# OpenROV_Light_Board_2_8.net
KiCad netlist of a schematic drawn in EAGLE
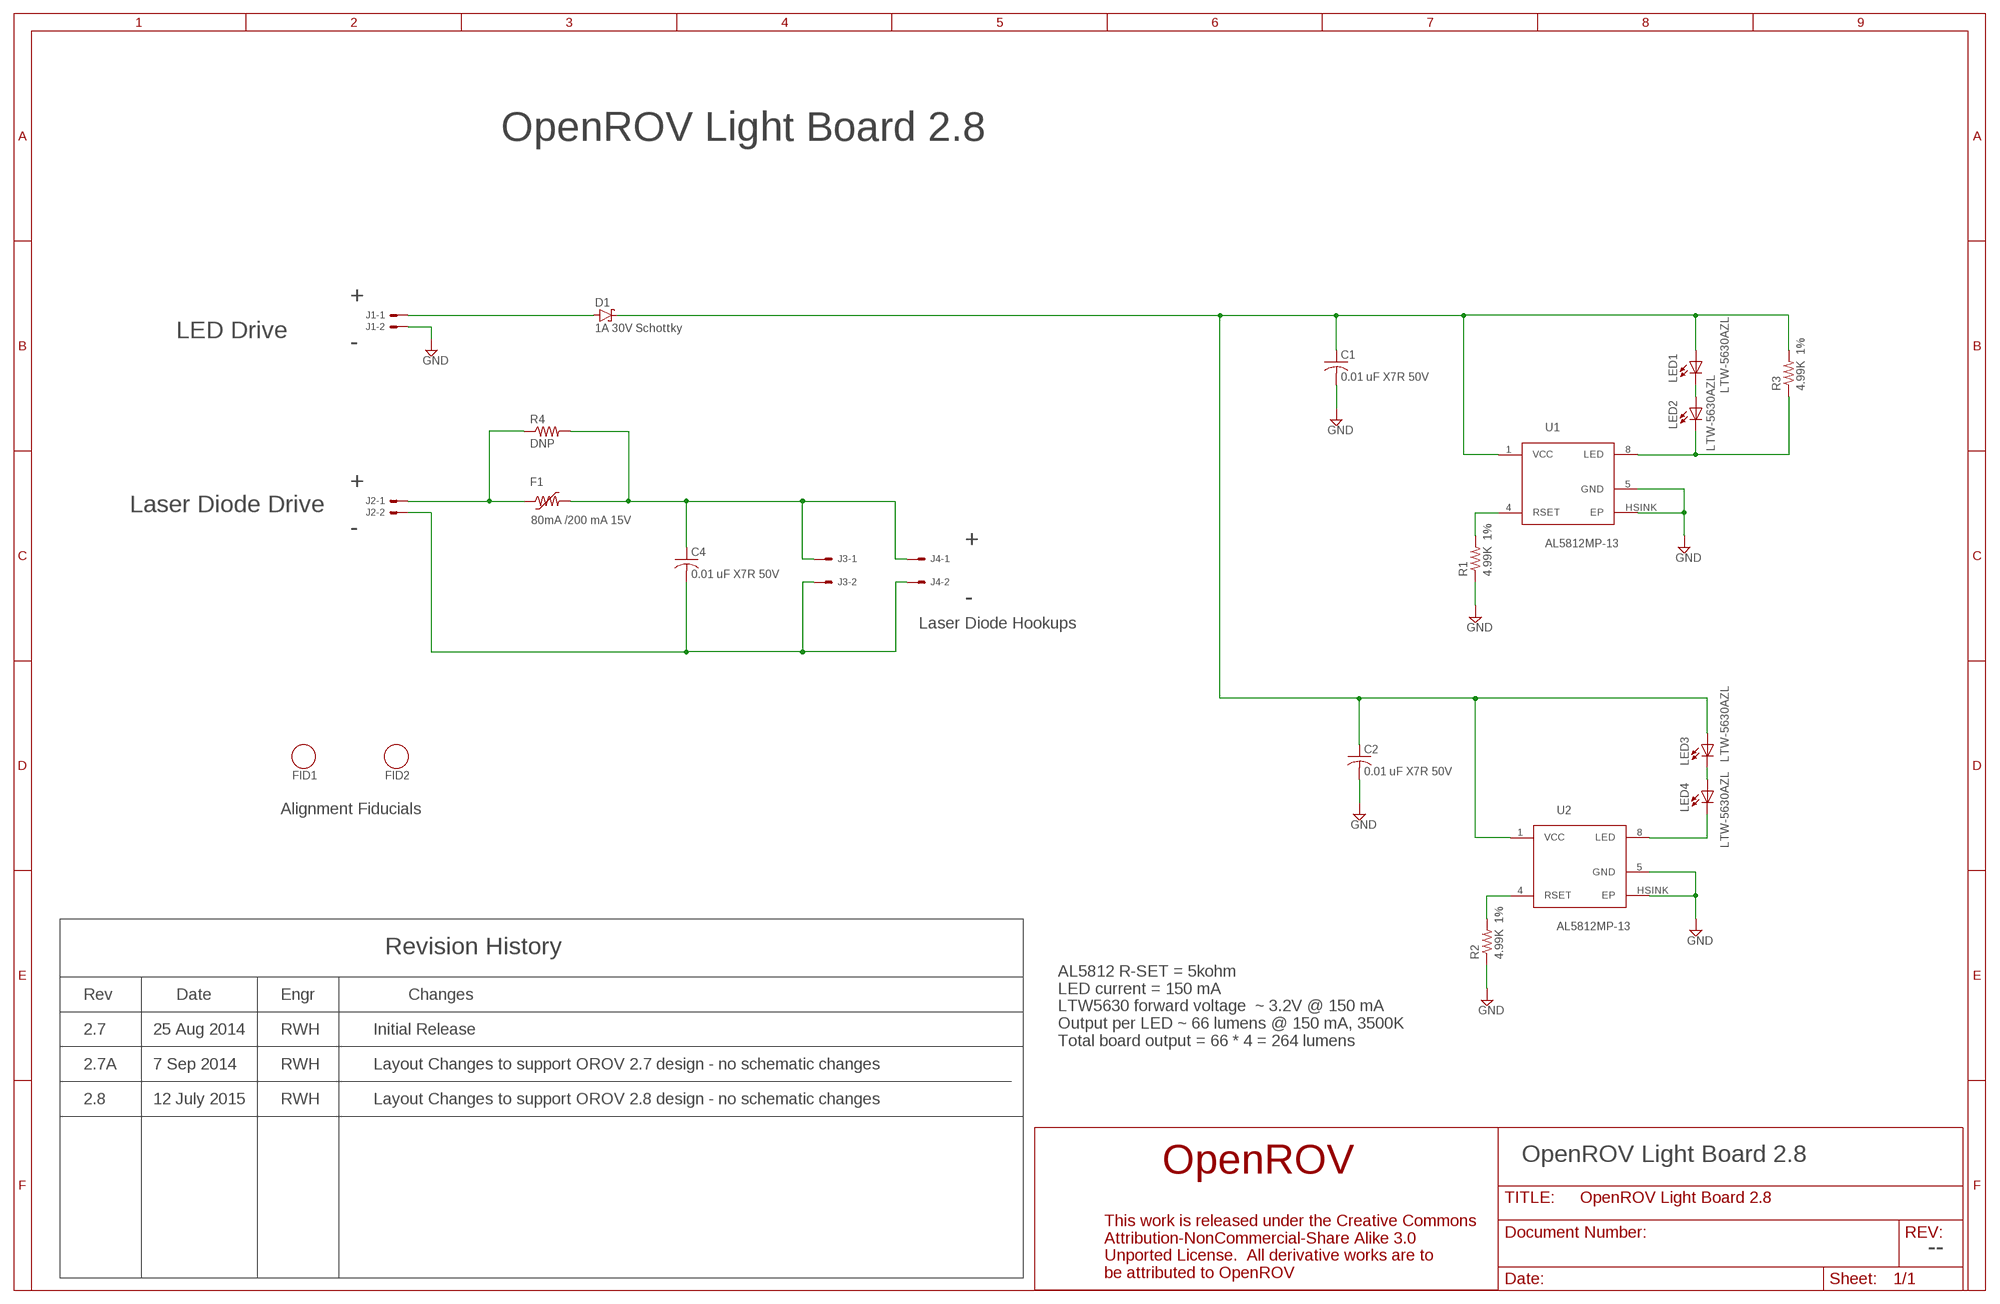
[diagram p0: schematic, sheet 1]

(export (version "E")
  (design (tool "Eeschema 10.0.6"))
  (components
    (comp (ref "C1")
      (value "0.01 uF X7R 50V")
      (footprint "eagle-import:R0603")
      (libsource (lib "eagle-import") (part "CAP0603"))
    )
    (comp (ref "C2")
      (value "0.01 uF X7R 50V")
      (footprint "eagle-import:R0603")
      (libsource (lib "eagle-import") (part "CAP0603"))
    )
    (comp (ref "C4")
      (value "0.01 uF X7R 50V")
      (footprint "eagle-import:R0603")
      (libsource (lib "eagle-import") (part "CAP0603"))
    )
    (comp (ref "D1")
      (value "1A 30V Schottky")
      (footprint "eagle-import:DO214AC")
      (libsource (lib "eagle-import") (part "SCHOTTKYDO214AC"))
    )
    (comp (ref "F1")
      (value "80mA /200 mA 15V")
      (footprint "eagle-import:R0603")
      (libsource (lib "eagle-import") (part "POLYFUSE-0603"))
    )
    (comp (ref "FID1")
      (value "FIDUCIAL_1")
      (footprint "eagle-import:FIDUCIAL_1")
      (libsource (lib "eagle-import") (part "FIDUCIAL_1"))
    )
    (comp (ref "FID2")
      (value "FIDUCIAL_1")
      (footprint "eagle-import:FIDUCIAL_1")
      (libsource (lib "eagle-import") (part "FIDUCIAL_1"))
    )
    (comp (ref "J1")
      (value "SOLDER_PADS_3MM")
      (footprint "eagle-import:SOLDER_PADS_3MM")
      (libsource (lib "eagle-import") (part "SOLDER_PADS_3MM"))
    )
    (comp (ref "J2")
      (value "SOLDER_PADS_3MM")
      (footprint "eagle-import:SOLDER_PADS_3MM")
      (libsource (lib "eagle-import") (part "SOLDER_PADS_3MM"))
    )
    (comp (ref "J3")
      (value "SOLDER_PADS_3MM-SMALL_HOLE")
      (footprint "eagle-import:SOLDER_PADS_3MM_SMALL_HOLE")
      (libsource (lib "eagle-import") (part "SOLDER_PADS_3MM-SMALL_HOLE"))
    )
    (comp (ref "J4")
      (value "SOLDER_PADS_3MM-SMALL_HOLE")
      (footprint "eagle-import:SOLDER_PADS_3MM_SMALL_HOLE")
      (libsource (lib "eagle-import") (part "SOLDER_PADS_3MM-SMALL_HOLE"))
    )
    (comp (ref "LED1")
      (value "LTW-5630AZL")
      (footprint "eagle-import:LITEON-5630")
      (libsource (lib "eagle-import") (part "LTW-5630AZL"))
    )
    (comp (ref "LED2")
      (value "LTW-5630AZL")
      (footprint "eagle-import:LITEON-5630")
      (libsource (lib "eagle-import") (part "LTW-5630AZL"))
    )
    (comp (ref "LED3")
      (value "LTW-5630AZL")
      (footprint "eagle-import:LITEON-5630")
      (libsource (lib "eagle-import") (part "LTW-5630AZL"))
    )
    (comp (ref "LED4")
      (value "LTW-5630AZL")
      (footprint "eagle-import:LITEON-5630")
      (libsource (lib "eagle-import") (part "LTW-5630AZL"))
    )
    (comp (ref "R1")
      (value "4.99K 1%")
      (footprint "eagle-import:R0603")
      (libsource (lib "eagle-import") (part "RESISTOR-0603"))
    )
    (comp (ref "R2")
      (value "4.99K 1%")
      (footprint "eagle-import:R0603")
      (libsource (lib "eagle-import") (part "RESISTOR-0603"))
    )
    (comp (ref "R3")
      (value "4.99K 1%")
      (footprint "eagle-import:R0603")
      (libsource (lib "eagle-import") (part "RESISTOR-0603"))
    )
    (comp (ref "R4")
      (value "DNP")
      (footprint "eagle-import:R1206")
      (libsource (lib "eagle-import") (part "RESISTOR-1206"))
    )
    (comp (ref "U1")
      (value "AL5812MP-13")
      (footprint "eagle-import:MSOP-8EP")
      (libsource (lib "eagle-import") (part "AL5812MP-13"))
    )
    (comp (ref "U2")
      (value "AL5812MP-13")
      (footprint "eagle-import:MSOP-8EP")
      (libsource (lib "eagle-import") (part "AL5812MP-13"))
    )
  )
  (nets
    (net (code "1") (name "GND") (class "Default")
      (node (ref "C1") (pin "2") (pinfunction "2_2") (pintype "passive"))
      (node (ref "C2") (pin "2") (pinfunction "2_2") (pintype "passive"))
      (node (ref "J1") (pin "2") (pinfunction "S_2") (pintype "passive"))
      (node (ref "R1") (pin "1") (pinfunction "1_1") (pintype "passive"))
      (node (ref "R2") (pin "1") (pinfunction "1_1") (pintype "passive"))
      (node (ref "U1") (pin "5") (pinfunction "GND_5") (pintype "bidirectional"))
      (node (ref "U1") (pin "HSINK") (pinfunction "EP_HSINK") (pintype "bidirectional"))
      (node (ref "U2") (pin "5") (pinfunction "GND_5") (pintype "bidirectional"))
      (node (ref "U2") (pin "HSINK") (pinfunction "EP_HSINK") (pintype "bidirectional"))
    )
    (net (code "2") (name "Net-(J1A-S)") (class "Default")
      (node (ref "D1") (pin "A") (pinfunction "A_A") (pintype "passive"))
      (node (ref "J1") (pin "1") (pinfunction "S_1") (pintype "passive"))
    )
    (net (code "3") (name "Net-(J2A-S)") (class "Default")
      (node (ref "F1") (pin "1") (pinfunction "1_1") (pintype "passive"))
      (node (ref "J2") (pin "1") (pinfunction "S_1") (pintype "passive"))
      (node (ref "R4") (pin "1") (pinfunction "1_1") (pintype "passive"))
    )
    (net (code "4") (name "Net-(J2B-S)") (class "Default")
      (node (ref "C4") (pin "2") (pinfunction "2_2") (pintype "passive"))
      (node (ref "J2") (pin "2") (pinfunction "S_2") (pintype "passive"))
      (node (ref "J3") (pin "2") (pinfunction "S_2") (pintype "passive"))
      (node (ref "J4") (pin "2") (pinfunction "S_2") (pintype "passive"))
    )
    (net (code "5") (name "Net-(J3A-S)") (class "Default")
      (node (ref "C4") (pin "1") (pinfunction "1_1") (pintype "passive"))
      (node (ref "F1") (pin "2") (pinfunction "2_2") (pintype "passive"))
      (node (ref "J3") (pin "1") (pinfunction "S_1") (pintype "passive"))
      (node (ref "J4") (pin "1") (pinfunction "S_1") (pintype "passive"))
      (node (ref "R4") (pin "2") (pinfunction "2_2") (pintype "passive"))
    )
    (net (code "6") (name "Net-(LED1-C-PadC1)") (class "Default")
      (node (ref "LED1") (pin "C1") (pinfunction "C_C1") (pintype "passive"))
      (node (ref "LED1") (pin "C2") (pinfunction "C_C2") (pintype "passive"))
      (node (ref "LED2") (pin "A1") (pinfunction "A_A1") (pintype "passive"))
      (node (ref "LED2") (pin "A2") (pinfunction "A_A2") (pintype "passive"))
      (node (ref "LED2") (pin "A3") (pinfunction "A_A3") (pintype "passive"))
    )
    (net (code "7") (name "Net-(LED3-C-PadC1)") (class "Default")
      (node (ref "LED3") (pin "C1") (pinfunction "C_C1") (pintype "passive"))
      (node (ref "LED3") (pin "C2") (pinfunction "C_C2") (pintype "passive"))
      (node (ref "LED4") (pin "A1") (pinfunction "A_A1") (pintype "passive"))
      (node (ref "LED4") (pin "A2") (pinfunction "A_A2") (pintype "passive"))
      (node (ref "LED4") (pin "A3") (pinfunction "A_A3") (pintype "passive"))
    )
    (net (code "8") (name "Net-(U1-LED)") (class "Default")
      (node (ref "LED2") (pin "C1") (pinfunction "C_C1") (pintype "passive"))
      (node (ref "LED2") (pin "C2") (pinfunction "C_C2") (pintype "passive"))
      (node (ref "R3") (pin "1") (pinfunction "1_1") (pintype "passive"))
      (node (ref "U1") (pin "8") (pinfunction "LED_8") (pintype "bidirectional"))
    )
    (net (code "9") (name "Net-(U1-RSET)") (class "Default")
      (node (ref "R1") (pin "2") (pinfunction "2_2") (pintype "passive"))
      (node (ref "U1") (pin "4") (pinfunction "RSET_4") (pintype "bidirectional"))
    )
    (net (code "10") (name "Net-(U1-VCC)") (class "Default")
      (node (ref "C1") (pin "1") (pinfunction "1_1") (pintype "passive"))
      (node (ref "C2") (pin "1") (pinfunction "1_1") (pintype "passive"))
      (node (ref "D1") (pin "C") (pinfunction "C_C") (pintype "passive"))
      (node (ref "LED1") (pin "A1") (pinfunction "A_A1") (pintype "passive"))
      (node (ref "LED1") (pin "A2") (pinfunction "A_A2") (pintype "passive"))
      (node (ref "LED1") (pin "A3") (pinfunction "A_A3") (pintype "passive"))
      (node (ref "LED3") (pin "A1") (pinfunction "A_A1") (pintype "passive"))
      (node (ref "LED3") (pin "A2") (pinfunction "A_A2") (pintype "passive"))
      (node (ref "LED3") (pin "A3") (pinfunction "A_A3") (pintype "passive"))
      (node (ref "R3") (pin "2") (pinfunction "2_2") (pintype "passive"))
      (node (ref "U1") (pin "1") (pinfunction "VCC_1") (pintype "bidirectional"))
      (node (ref "U2") (pin "1") (pinfunction "VCC_1") (pintype "bidirectional"))
    )
    (net (code "11") (name "Net-(U2-LED)") (class "Default")
      (node (ref "LED4") (pin "C1") (pinfunction "C_C1") (pintype "passive"))
      (node (ref "LED4") (pin "C2") (pinfunction "C_C2") (pintype "passive"))
      (node (ref "U2") (pin "8") (pinfunction "LED_8") (pintype "bidirectional"))
    )
    (net (code "12") (name "Net-(U2-RSET)") (class "Default")
      (node (ref "R2") (pin "2") (pinfunction "2_2") (pintype "passive"))
      (node (ref "U2") (pin "4") (pinfunction "RSET_4") (pintype "bidirectional"))
    )
  )
)
